# Tape.net
KiCad netlist of a schematic drawn in EAGLE
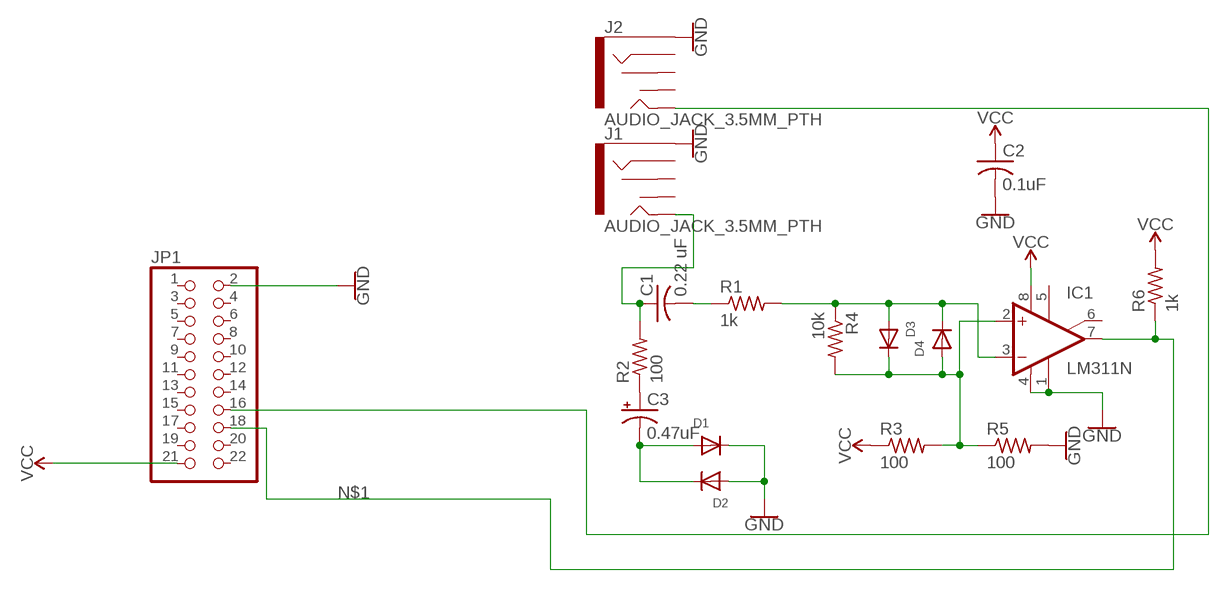
[diagram p0: schematic, sheet 1]

(export (version "E")
  (design (tool "Eeschema 10.0.6"))
  (components
    (comp (ref "C1")
      (value "0.22 uF")
      (footprint "eagle-import:C025-030X050")
      (libsource (lib "eagle-import") (part "C-US025-030X050"))
    )
    (comp (ref "C2")
      (value "0.1uF")
      (footprint "eagle-import:C025-030X050")
      (libsource (lib "eagle-import") (part "C-US025-030X050"))
    )
    (comp (ref "C3")
      (value "0.47uF")
      (footprint "eagle-import:E2,5-5")
      (libsource (lib "eagle-import") (part "CPOL-USE2.5-5"))
    )
    (comp (ref "D1")
      (value "DIODEDO-1N4148")
      (footprint "eagle-import:DO-1N4148")
      (libsource (lib "eagle-import") (part "DIODEDO-1N4148"))
    )
    (comp (ref "D2")
      (value "DIODEDO-1N4148")
      (footprint "eagle-import:DO-1N4148")
      (libsource (lib "eagle-import") (part "DIODEDO-1N4148"))
    )
    (comp (ref "D3")
      (value "DIODEDO-1N4148")
      (footprint "eagle-import:DO-1N4148")
      (libsource (lib "eagle-import") (part "DIODEDO-1N4148"))
    )
    (comp (ref "D4")
      (value "DIODEDO-1N4148")
      (footprint "eagle-import:DO-1N4148")
      (libsource (lib "eagle-import") (part "DIODEDO-1N4148"))
    )
    (comp (ref "IC1")
      (value "LM311N")
      (footprint "eagle-import:DIL08")
      (libsource (lib "eagle-import") (part "LM311N"))
    )
    (comp (ref "J1")
      (value "AUDIO_JACK_3.5MM_PTH")
      (footprint "eagle-import:AUDIO-JACK")
      (libsource (lib "eagle-import") (part "AUDIO_JACK_3.5MM_PTH"))
    )
    (comp (ref "J2")
      (value "AUDIO_JACK_3.5MM_PTH")
      (footprint "eagle-import:AUDIO-JACK")
      (libsource (lib "eagle-import") (part "AUDIO_JACK_3.5MM_PTH"))
    )
    (comp (ref "JP1")
      (value "PINHD-2X11/90")
      (footprint "eagle-import:2X11_90")
      (libsource (lib "eagle-import") (part "PINHD-2X11/90"))
    )
    (comp (ref "R1")
      (value "1k")
      (footprint "eagle-import:0204_7")
      (libsource (lib "eagle-import") (part "R-US_0204/7"))
    )
    (comp (ref "R2")
      (value "100")
      (footprint "eagle-import:0204_7")
      (libsource (lib "eagle-import") (part "R-US_0204/7"))
    )
    (comp (ref "R3")
      (value "100")
      (footprint "eagle-import:0204_7")
      (libsource (lib "eagle-import") (part "R-US_0204/7"))
    )
    (comp (ref "R4")
      (value "10k")
      (footprint "eagle-import:0204_7")
      (libsource (lib "eagle-import") (part "R-US_0204/7"))
    )
    (comp (ref "R5")
      (value "100")
      (footprint "eagle-import:0204_7")
      (libsource (lib "eagle-import") (part "R-US_0204/7"))
    )
    (comp (ref "R6")
      (value "1k")
      (footprint "eagle-import:0204_7")
      (libsource (lib "eagle-import") (part "R-US_0204/7"))
    )
  )
  (nets
    (net (code "1") (name "/N$1") (class "Default")
      (node (ref "IC1") (pin "7") (pinfunction "OUT_7") (pintype "output"))
      (node (ref "JP1") (pin "18") (pinfunction "18_18") (pintype "passive"))
      (node (ref "R6") (pin "1") (pinfunction "1_1") (pintype "passive"))
    )
    (net (code "2") (name "GND") (class "Default")
      (node (ref "C2") (pin "2") (pinfunction "2_2") (pintype "passive"))
      (node (ref "D1") (pin "C") (pinfunction "C_C") (pintype "passive"))
      (node (ref "D2") (pin "A") (pinfunction "A_A") (pintype "passive"))
      (node (ref "IC1") (pin "1") (pinfunction "GND_1") (pintype "passive"))
      (node (ref "IC1") (pin "4") (pinfunction "V-_4") (pintype "power_in"))
      (node (ref "J1") (pin "SLEEVE") (pinfunction "SLEEVE_SLEEVE") (pintype "bidirectional"))
      (node (ref "J2") (pin "SLEEVE") (pinfunction "SLEEVE_SLEEVE") (pintype "bidirectional"))
      (node (ref "JP1") (pin "2") (pinfunction "2_2") (pintype "passive"))
      (node (ref "R5") (pin "2") (pinfunction "2_2") (pintype "passive"))
    )
    (net (code "3") (name "Net-(C1-Pad1)") (class "Default")
      (node (ref "C1") (pin "1") (pinfunction "1_1") (pintype "passive"))
      (node (ref "J1") (pin "TIP") (pinfunction "TIP_TIP") (pintype "bidirectional"))
      (node (ref "R2") (pin "2") (pinfunction "2_2") (pintype "passive"))
    )
    (net (code "4") (name "Net-(C1-Pad2)") (class "Default")
      (node (ref "C1") (pin "2") (pinfunction "2_2") (pintype "passive"))
      (node (ref "R1") (pin "1") (pinfunction "1_1") (pintype "passive"))
    )
    (net (code "5") (name "Net-(C3-Pad+)") (class "Default")
      (node (ref "C3") (pin "+") (pinfunction "+_+") (pintype "passive"))
      (node (ref "R2") (pin "1") (pinfunction "1_1") (pintype "passive"))
    )
    (net (code "6") (name "Net-(C3-Pad-)") (class "Default")
      (node (ref "C3") (pin "-") (pinfunction "-_-") (pintype "passive"))
      (node (ref "D1") (pin "A") (pinfunction "A_A") (pintype "passive"))
      (node (ref "D2") (pin "C") (pinfunction "C_C") (pintype "passive"))
    )
    (net (code "7") (name "Net-(IC1-+IN)") (class "Default")
      (node (ref "D3") (pin "C") (pinfunction "C_C") (pintype "passive"))
      (node (ref "D4") (pin "A") (pinfunction "A_A") (pintype "passive"))
      (node (ref "IC1") (pin "2") (pinfunction "+IN_2") (pintype "input"))
      (node (ref "R3") (pin "2") (pinfunction "2_2") (pintype "passive"))
      (node (ref "R4") (pin "2") (pinfunction "2_2") (pintype "passive"))
      (node (ref "R5") (pin "1") (pinfunction "1_1") (pintype "passive"))
    )
    (net (code "8") (name "Net-(IC1--IN)") (class "Default")
      (node (ref "D3") (pin "A") (pinfunction "A_A") (pintype "passive"))
      (node (ref "D4") (pin "C") (pinfunction "C_C") (pintype "passive"))
      (node (ref "IC1") (pin "3") (pinfunction "-IN_3") (pintype "input"))
      (node (ref "R1") (pin "2") (pinfunction "2_2") (pintype "passive"))
      (node (ref "R4") (pin "1") (pinfunction "1_1") (pintype "passive"))
    )
    (net (code "9") (name "Net-(J2-PadTIP)") (class "Default")
      (node (ref "J2") (pin "TIP") (pinfunction "TIP_TIP") (pintype "bidirectional"))
      (node (ref "JP1") (pin "16") (pinfunction "16_16") (pintype "passive"))
    )
    (net (code "10") (name "VCC") (class "Default")
      (node (ref "C2") (pin "1") (pinfunction "1_1") (pintype "passive"))
      (node (ref "IC1") (pin "8") (pinfunction "V+_8") (pintype "power_in"))
      (node (ref "JP1") (pin "21") (pinfunction "21_21") (pintype "passive"))
      (node (ref "R3") (pin "1") (pinfunction "1_1") (pintype "passive"))
      (node (ref "R6") (pin "2") (pinfunction "2_2") (pintype "passive"))
    )
    (net (code "11") (name "unconnected-(IC1-ON-Pad5)") (class "Default")
      (node (ref "IC1") (pin "5") (pinfunction "ON_5") (pintype "passive"))
    )
    (net (code "12") (name "unconnected-(IC1-ON{slash}STR-Pad6)") (class "Default")
      (node (ref "IC1") (pin "6") (pinfunction "ON/STR_6") (pintype "passive"))
    )
    (net (code "13") (name "unconnected-(J1-PadRING)") (class "Default")
      (node (ref "J1") (pin "RING") (pinfunction "RING_RING") (pintype "bidirectional"))
    )
    (net (code "14") (name "unconnected-(J1-PadRSH)") (class "Default")
      (node (ref "J1") (pin "RSH") (pinfunction "RSH_RSH") (pintype "bidirectional"))
    )
    (net (code "15") (name "unconnected-(J1-PadTSH)") (class "Default")
      (node (ref "J1") (pin "TSH") (pinfunction "TSH_TSH") (pintype "bidirectional"))
    )
    (net (code "16") (name "unconnected-(J2-PadRING)") (class "Default")
      (node (ref "J2") (pin "RING") (pinfunction "RING_RING") (pintype "bidirectional"))
    )
    (net (code "17") (name "unconnected-(J2-PadRSH)") (class "Default")
      (node (ref "J2") (pin "RSH") (pinfunction "RSH_RSH") (pintype "bidirectional"))
    )
    (net (code "18") (name "unconnected-(J2-PadTSH)") (class "Default")
      (node (ref "J2") (pin "TSH") (pinfunction "TSH_TSH") (pintype "bidirectional"))
    )
    (net (code "19") (name "unconnected-(JP1-Pad1)") (class "Default")
      (node (ref "JP1") (pin "1") (pinfunction "1_1") (pintype "passive"))
    )
    (net (code "20") (name "unconnected-(JP1-Pad3)") (class "Default")
      (node (ref "JP1") (pin "3") (pinfunction "3_3") (pintype "passive"))
    )
    (net (code "21") (name "unconnected-(JP1-Pad4)") (class "Default")
      (node (ref "JP1") (pin "4") (pinfunction "4_4") (pintype "passive"))
    )
    (net (code "22") (name "unconnected-(JP1-Pad5)") (class "Default")
      (node (ref "JP1") (pin "5") (pinfunction "5_5") (pintype "passive"))
    )
    (net (code "23") (name "unconnected-(JP1-Pad6)") (class "Default")
      (node (ref "JP1") (pin "6") (pinfunction "6_6") (pintype "passive"))
    )
    (net (code "24") (name "unconnected-(JP1-Pad7)") (class "Default")
      (node (ref "JP1") (pin "7") (pinfunction "7_7") (pintype "passive"))
    )
    (net (code "25") (name "unconnected-(JP1-Pad8)") (class "Default")
      (node (ref "JP1") (pin "8") (pinfunction "8_8") (pintype "passive"))
    )
    (net (code "26") (name "unconnected-(JP1-Pad9)") (class "Default")
      (node (ref "JP1") (pin "9") (pinfunction "9_9") (pintype "passive"))
    )
    (net (code "27") (name "unconnected-(JP1-Pad10)") (class "Default")
      (node (ref "JP1") (pin "10") (pinfunction "10_10") (pintype "passive"))
    )
    (net (code "28") (name "unconnected-(JP1-Pad11)") (class "Default")
      (node (ref "JP1") (pin "11") (pinfunction "11_11") (pintype "passive"))
    )
    (net (code "29") (name "unconnected-(JP1-Pad12)") (class "Default")
      (node (ref "JP1") (pin "12") (pinfunction "12_12") (pintype "passive"))
    )
    (net (code "30") (name "unconnected-(JP1-Pad13)") (class "Default")
      (node (ref "JP1") (pin "13") (pinfunction "13_13") (pintype "passive"))
    )
    (net (code "31") (name "unconnected-(JP1-Pad14)") (class "Default")
      (node (ref "JP1") (pin "14") (pinfunction "14_14") (pintype "passive"))
    )
    (net (code "32") (name "unconnected-(JP1-Pad15)") (class "Default")
      (node (ref "JP1") (pin "15") (pinfunction "15_15") (pintype "passive"))
    )
    (net (code "33") (name "unconnected-(JP1-Pad17)") (class "Default")
      (node (ref "JP1") (pin "17") (pinfunction "17_17") (pintype "passive"))
    )
    (net (code "34") (name "unconnected-(JP1-Pad19)") (class "Default")
      (node (ref "JP1") (pin "19") (pinfunction "19_19") (pintype "passive"))
    )
    (net (code "35") (name "unconnected-(JP1-Pad20)") (class "Default")
      (node (ref "JP1") (pin "20") (pinfunction "20_20") (pintype "passive"))
    )
    (net (code "36") (name "unconnected-(JP1-Pad22)") (class "Default")
      (node (ref "JP1") (pin "22") (pinfunction "22_22") (pintype "passive"))
    )
  )
)
